# SCH_Business-Card_2024-06-13.net
KiCad netlist of a schematic drawn in EasyEDA
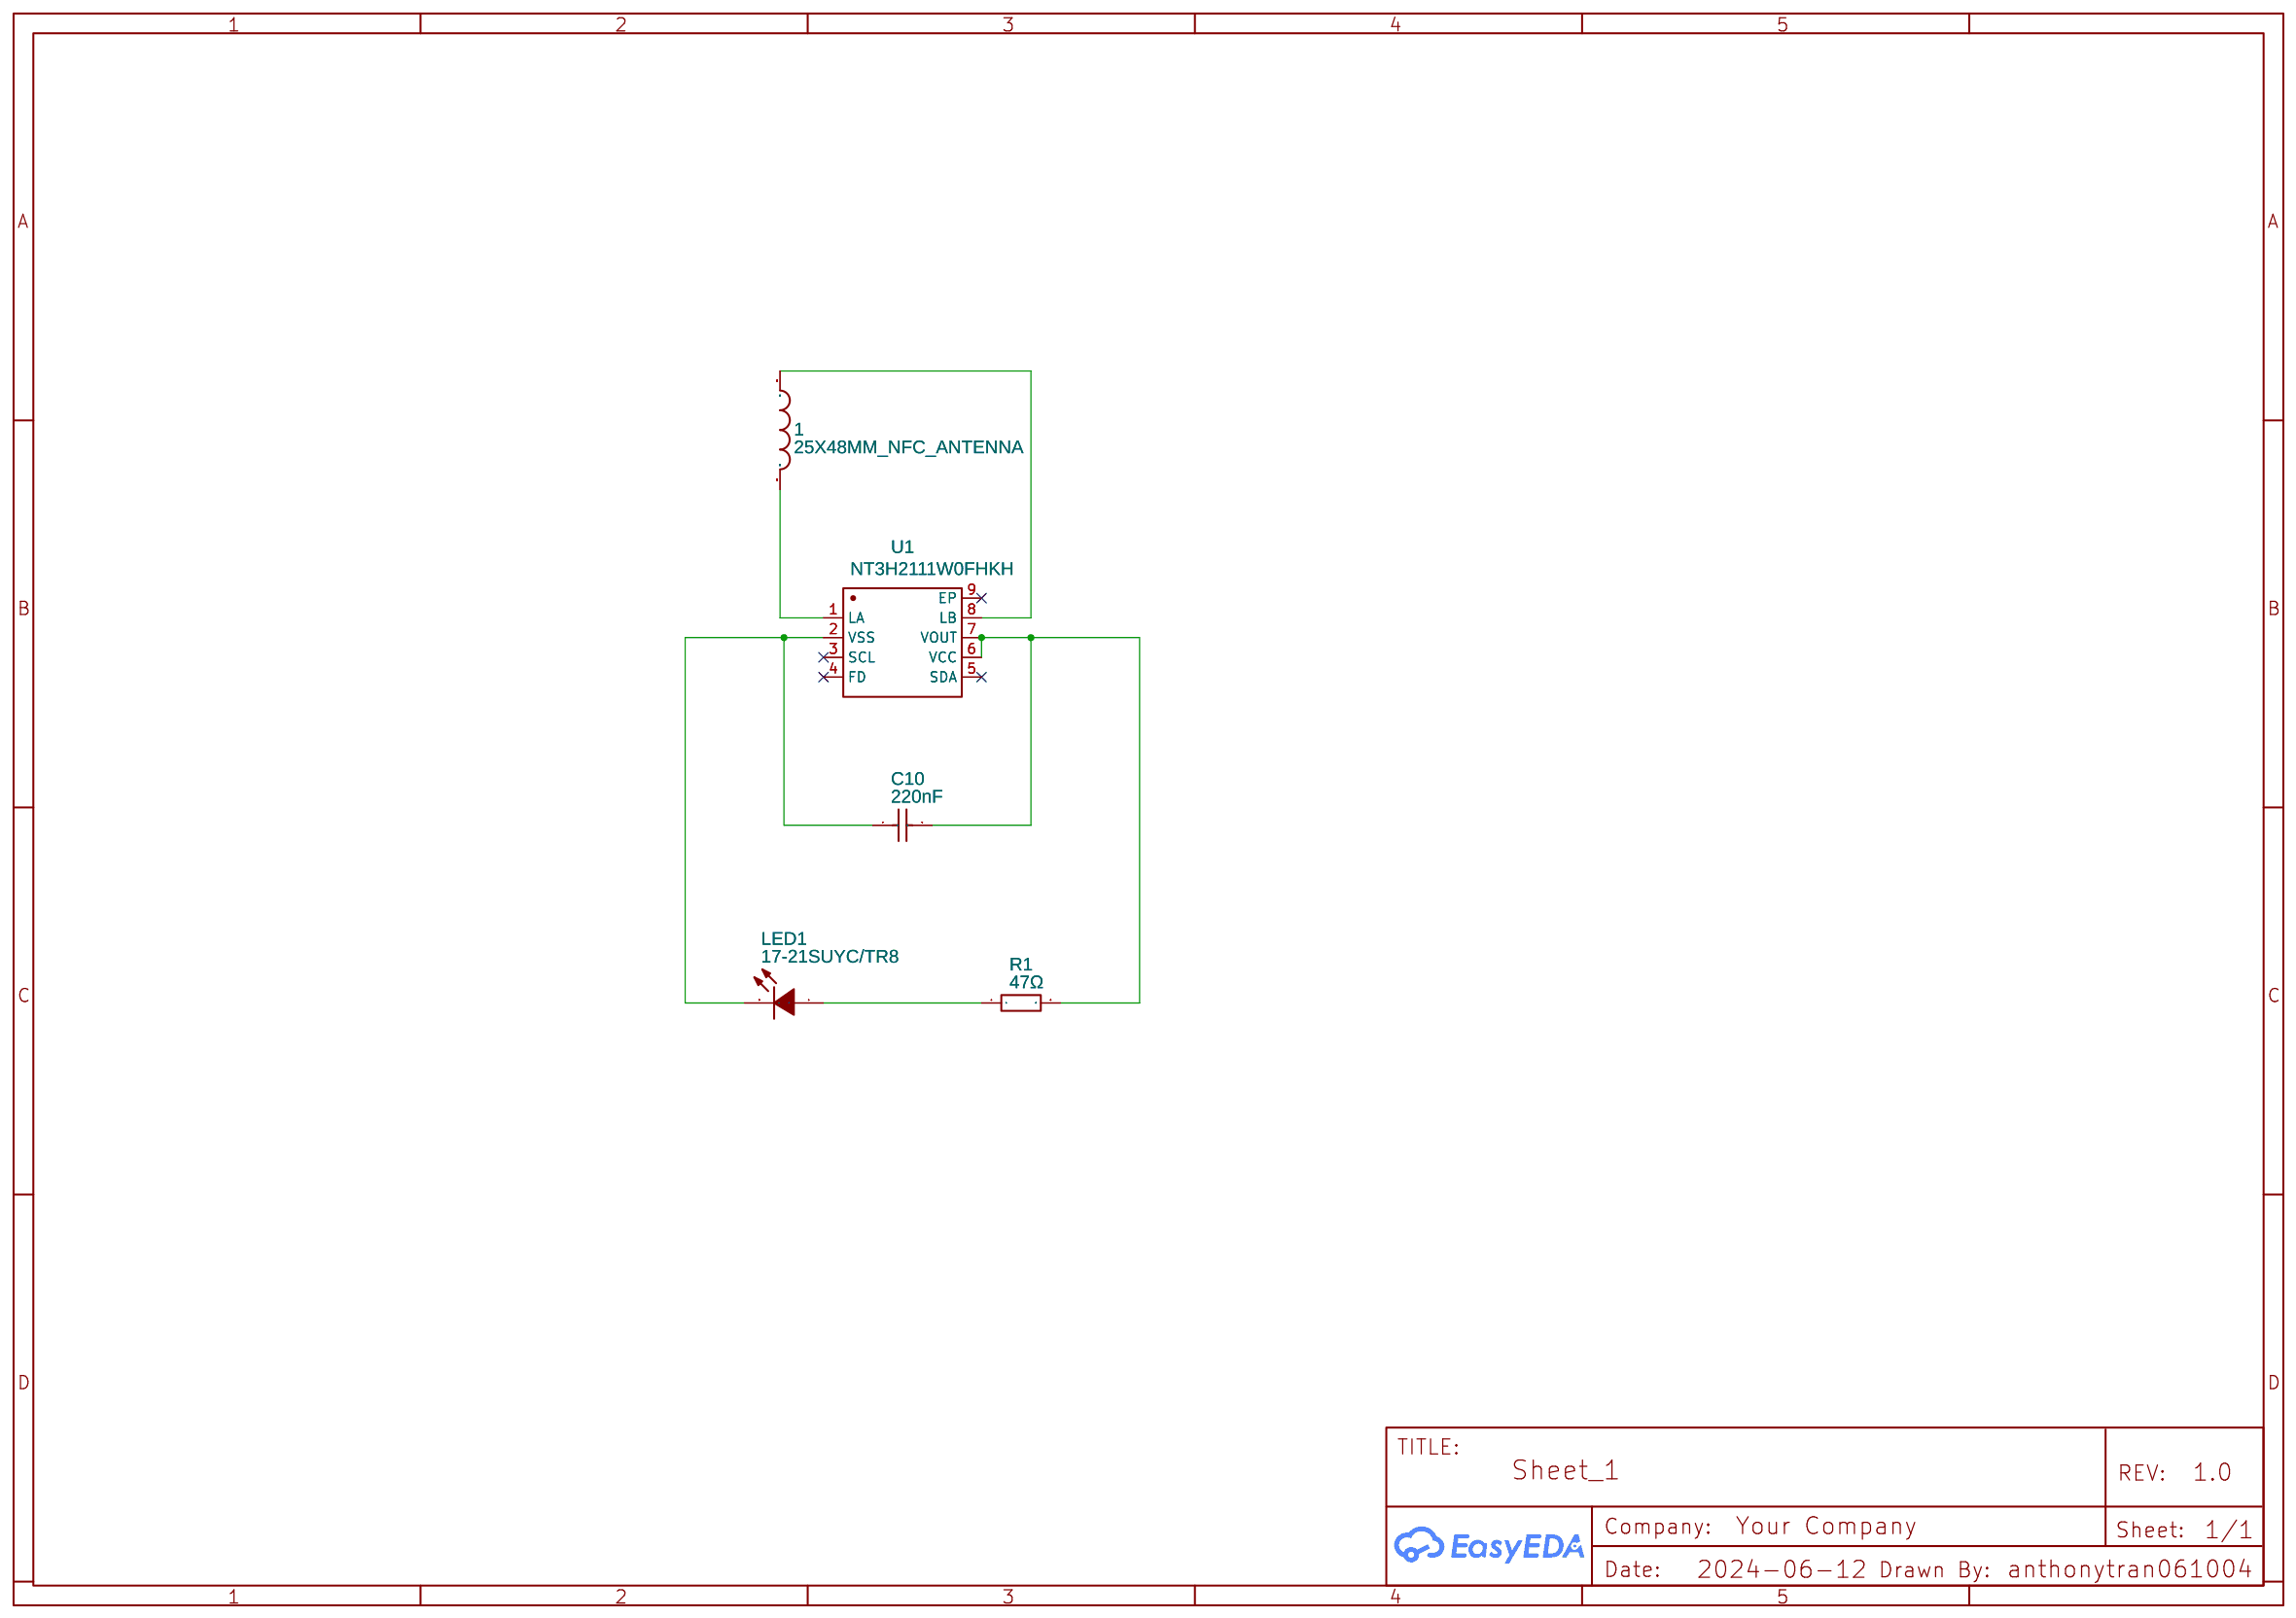
[diagram p0: schematic sheet]

(export (version "E")
  (design (tool "Eeschema 10.0.6"))
  (components
    (comp (ref "1") (value "25X48MM_NFC_ANTENNA") (libsource (lib "") (part "25X48MM_NFC_ANTENNA")))
    (comp (ref "C10")
      (value "220nF")
      (fields
        (field (name "Manufacturer Part") "CL10B224KA8NNNC")
        (field (name "Manufacturer") "SAMSUNG(三星)")
      )
      (libsource (lib "") (part "CL10B224KA8NNNC"))
    )
    (comp (ref "LED1")
      (value "17-21SUYC/TR8")
      (fields (field (name "Manufacturer Part") "KT-0805黄灯") (field (name "Manufacturer") "KENTO"))
      (libsource (lib "") (part "17-21SUYC/TR8"))
    )
    (comp (ref "R1")
      (value "47Ω")
      (fields
        (field (name "Manufacturer Part") "0603WAF470JT5E")
        (field (name "Manufacturer") "UNI-ROYAL(厚声)")
      )
      (libsource (lib "") (part "0603WAF470JT5E"))
    )
    (comp (ref "U1")
      (value "NT3H2111W0FHKH")
      (fields (field (name "Manufacturer") "NXP(恩智浦)"))
      (libsource (lib "") (part "NT3H2111W0FHKH"))
    )
  )
  (nets
    (net (code "1") (name "Net-(LED1-+)") (class "Default")
      (node (ref "LED1") (pin "1") (pinfunction "+_1") (pintype "unspecified"))
      (node (ref "R1") (pin "1") (pinfunction "1_1") (pintype "input"))
    )
    (net (code "2") (name "Net-(LED1--)") (class "Default")
      (node (ref "C10") (pin "1") (pinfunction "1_1") (pintype "input"))
      (node (ref "LED1") (pin "2") (pinfunction "-_2") (pintype "unspecified"))
      (node (ref "U1") (pin "2") (pinfunction "VSS_2") (pintype "unspecified"))
    )
    (net (code "3") (name "Net-(U1-LA)") (class "Default")
      (node (ref "1") (pin "P$2") (pinfunction "P$2_P$2") (pintype "bidirectional"))
      (node (ref "U1") (pin "1") (pinfunction "LA_1") (pintype "unspecified"))
    )
    (net (code "4") (name "Net-(U1-LB)") (class "Default")
      (node (ref "1") (pin "P$1") (pinfunction "P$1_P$1") (pintype "bidirectional"))
      (node (ref "U1") (pin "8") (pinfunction "LB_8") (pintype "unspecified"))
    )
    (net (code "5") (name "Net-(U1-VCC)") (class "Default")
      (node (ref "C10") (pin "2") (pinfunction "2_2") (pintype "input"))
      (node (ref "R1") (pin "2") (pinfunction "2_2") (pintype "input"))
      (node (ref "U1") (pin "6") (pinfunction "VCC_6") (pintype "unspecified"))
      (node (ref "U1") (pin "7") (pinfunction "VOUT_7") (pintype "unspecified"))
    )
    (net (code "6") (name "unconnected-(U1-EP-Pad9)") (class "Default")
      (node (ref "U1") (pin "9") (pinfunction "EP_9") (pintype "unspecified+no_connect"))
    )
    (net (code "7") (name "unconnected-(U1-FD-Pad4)") (class "Default")
      (node (ref "U1") (pin "4") (pinfunction "FD_4") (pintype "unspecified+no_connect"))
    )
    (net (code "8") (name "unconnected-(U1-SCL-Pad3)") (class "Default")
      (node (ref "U1") (pin "3") (pinfunction "SCL_3") (pintype "unspecified+no_connect"))
    )
    (net (code "9") (name "unconnected-(U1-SDA-Pad5)") (class "Default")
      (node (ref "U1") (pin "5") (pinfunction "SDA_5") (pintype "unspecified+no_connect"))
    )
  )
)
